# HealcareSystem.net
KiCad netlist of a schematic drawn in Altium Designer
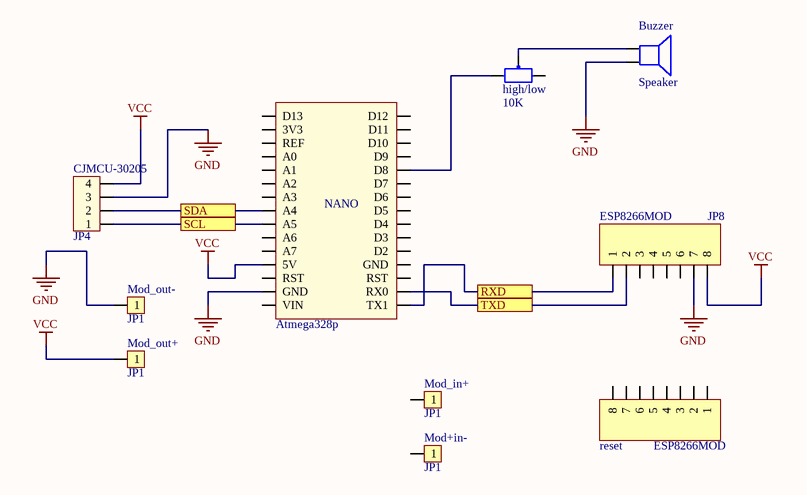
[diagram p0: HealcareSystem.SchDoc]

(export (version "E")
  (design (tool "Eeschema 10.0.6"))
  (components
    (comp (ref "Atmega328p")
      (value "Arduino Nano")
      (footprint "Arduino Nano")
      (description "Arduino NANO")
      (libsource (lib "LIBRARY") (part "Arduino Nano"))
    )
    (comp (ref "Buzzer")
      (value "Speaker")
      (footprint "SPEAKER")
      (description "Loudspeaker")
      (fields (field (name "PUBLISHER") "Altium Limited"))
      (libsource (lib "LIBRARY") (part "Speaker"))
    )
    (comp (ref "CJMCU-30205")
      (value "JP4")
      (footprint "CON4")
      (description "Connector 4")
      (libsource (lib "Library AL") (part "Con4"))
    )
    (comp (ref "ESP8266MOD")
      (value "JP8")
      (footprint "JP8-C1T")
      (description "WR-PHD 2.54 mm Angled Socket Header")
      (fields
        (field (name "MANUFACTURER") "Würth Elektronik eiSos GmbH")
        (field (name "PARTNO") "613008143121")
        (field (name "CREATED BY") "Karrer Zheng")
      )
      (libsource (lib "Library1") (part "JP8"))
    )
    (comp (ref "high/low")
      (value "10K")
      (footprint "VR")
      (description "Var Resistor")
      (libsource (lib "Library AL") (part "VR"))
    )
    (comp (ref "Mod+in-")
      (value "JP1")
      (footprint "JP1-D1T")
      (description "WR-PHD 2.54 mm Angled Socket Header")
      (fields
        (field (name "MANUFACTURER") "Würth Elektronik eiSos GmbH")
        (field (name "PARTNO") "613002143121")
        (field (name "CREATED BY") "Karrer Zheng")
      )
      (libsource (lib "LIBRARY") (part "JP1"))
    )
    (comp (ref "Mod_in+")
      (value "JP1")
      (footprint "JP1-D1T")
      (description "WR-PHD 2.54 mm Angled Socket Header")
      (fields
        (field (name "MANUFACTURER") "Würth Elektronik eiSos GmbH")
        (field (name "PARTNO") "613002143121")
        (field (name "CREATED BY") "Karrer Zheng")
      )
      (libsource (lib "LIBRARY") (part "JP1"))
    )
    (comp (ref "Mod_out+")
      (value "JP1")
      (footprint "JP1-D1T")
      (description "WR-PHD 2.54 mm Angled Socket Header")
      (fields
        (field (name "MANUFACTURER") "Würth Elektronik eiSos GmbH")
        (field (name "PARTNO") "613002143121")
        (field (name "CREATED BY") "Karrer Zheng")
      )
      (libsource (lib "LIBRARY") (part "JP1"))
    )
    (comp (ref "Mod_out-")
      (value "JP1")
      (footprint "JP1-D1T")
      (description "WR-PHD 2.54 mm Angled Socket Header")
      (fields
        (field (name "MANUFACTURER") "Würth Elektronik eiSos GmbH")
        (field (name "PARTNO") "613002143121")
        (field (name "CREATED BY") "Karrer Zheng")
      )
      (libsource (lib "LIBRARY") (part "JP1"))
    )
    (comp (ref "reset")
      (value "ESP8266MOD")
      (footprint "JP8-C1T")
      (description "WR-PHD 2.54 mm Angled Socket Header")
      (fields
        (field (name "MANUFACTURER") "Würth Elektronik eiSos GmbH")
        (field (name "PARTNO") "613008143121")
        (field (name "CREATED BY") "Karrer Zheng")
      )
      (libsource (lib "") (part "JP8_1"))
    )
  )
  (nets
    (net (code "1") (name "/RXD") (class "Default")
      (node (ref "Atmega328p") (pin "TX1") (pinfunction "TX1_TX1") (pintype "passive"))
      (node (ref "ESP8266MOD") (pin "1") (pinfunction "1_1") (pintype "passive"))
    )
    (net (code "2") (name "/SCL") (class "Default")
      (node (ref "Atmega328p") (pin "A5") (pinfunction "A5_A5") (pintype "passive"))
      (node (ref "CJMCU-30205") (pin "1") (pinfunction "1_1") (pintype "passive"))
    )
    (net (code "3") (name "/SDA") (class "Default")
      (node (ref "Atmega328p") (pin "A4") (pinfunction "A4_A4") (pintype "passive"))
      (node (ref "CJMCU-30205") (pin "2") (pinfunction "2_2") (pintype "passive"))
    )
    (net (code "4") (name "/TXD") (class "Default")
      (node (ref "Atmega328p") (pin "RX0") (pinfunction "RX0_RX0") (pintype "passive"))
      (node (ref "ESP8266MOD") (pin "2") (pinfunction "2_2") (pintype "passive"))
    )
    (net (code "5") (name "GND") (class "Default")
      (node (ref "Atmega328p") (pin "GND") (pinfunction "GND_GND") (pintype "passive"))
      (node (ref "Buzzer") (pin "2") (pinfunction "2_2") (pintype "passive"))
      (node (ref "CJMCU-30205") (pin "3") (pinfunction "3_3") (pintype "passive"))
      (node (ref "ESP8266MOD") (pin "7") (pinfunction "7_7") (pintype "passive"))
      (node (ref "Mod_out-") (pin "1") (pinfunction "1_1") (pintype "passive"))
    )
    (net (code "6") (name "Net-(Atmega328p-PadD8)") (class "Default")
      (node (ref "Atmega328p") (pin "D8") (pinfunction "D8_D8") (pintype "passive"))
      (node (ref "high/low") (pin "1") (pinfunction "1_1") (pintype "passive"))
    )
    (net (code "7") (name "Net-(Buzzer-Pad1)") (class "Default")
      (node (ref "Buzzer") (pin "1") (pinfunction "1_1") (pintype "passive"))
      (node (ref "high/low") (pin "2") (pinfunction "2_2") (pintype "passive"))
    )
    (net (code "8") (name "VCC") (class "Default")
      (node (ref "Atmega328p") (pin "5V") (pinfunction "5V_5V") (pintype "passive"))
      (node (ref "CJMCU-30205") (pin "4") (pinfunction "4_4") (pintype "passive"))
      (node (ref "ESP8266MOD") (pin "8") (pinfunction "8_8") (pintype "passive"))
      (node (ref "Mod_out+") (pin "1") (pinfunction "1_1") (pintype "passive"))
    )
    (net (code "9") (name "unconnected-(Atmega328p-Pad3V3)") (class "Default")
      (node (ref "Atmega328p") (pin "3V3") (pinfunction "3V3_3V3") (pintype "passive"))
    )
    (net (code "10") (name "unconnected-(Atmega328p-PadA0)") (class "Default")
      (node (ref "Atmega328p") (pin "A0") (pinfunction "A0_A0") (pintype "passive"))
    )
    (net (code "11") (name "unconnected-(Atmega328p-PadA1)") (class "Default")
      (node (ref "Atmega328p") (pin "A1") (pinfunction "A1_A1") (pintype "passive"))
    )
    (net (code "12") (name "unconnected-(Atmega328p-PadA2)") (class "Default")
      (node (ref "Atmega328p") (pin "A2") (pinfunction "A2_A2") (pintype "passive"))
    )
    (net (code "13") (name "unconnected-(Atmega328p-PadA3)") (class "Default")
      (node (ref "Atmega328p") (pin "A3") (pinfunction "A3_A3") (pintype "passive"))
    )
    (net (code "14") (name "unconnected-(Atmega328p-PadA6)") (class "Default")
      (node (ref "Atmega328p") (pin "A6") (pinfunction "A6_A6") (pintype "passive"))
    )
    (net (code "15") (name "unconnected-(Atmega328p-PadA7)") (class "Default")
      (node (ref "Atmega328p") (pin "A7") (pinfunction "A7_A7") (pintype "passive"))
    )
    (net (code "16") (name "unconnected-(Atmega328p-PadD2)") (class "Default")
      (node (ref "Atmega328p") (pin "D2") (pinfunction "D2_D2") (pintype "passive"))
    )
    (net (code "17") (name "unconnected-(Atmega328p-PadD3)") (class "Default")
      (node (ref "Atmega328p") (pin "D3") (pinfunction "D3_D3") (pintype "passive"))
    )
    (net (code "18") (name "unconnected-(Atmega328p-PadD4)") (class "Default")
      (node (ref "Atmega328p") (pin "D4") (pinfunction "D4_D4") (pintype "passive"))
    )
    (net (code "19") (name "unconnected-(Atmega328p-PadD5)") (class "Default")
      (node (ref "Atmega328p") (pin "D5") (pinfunction "D5_D5") (pintype "passive"))
    )
    (net (code "20") (name "unconnected-(Atmega328p-PadD6)") (class "Default")
      (node (ref "Atmega328p") (pin "D6") (pinfunction "D6_D6") (pintype "passive"))
    )
    (net (code "21") (name "unconnected-(Atmega328p-PadD7)") (class "Default")
      (node (ref "Atmega328p") (pin "D7") (pinfunction "D7_D7") (pintype "passive"))
    )
    (net (code "22") (name "unconnected-(Atmega328p-PadD9)") (class "Default")
      (node (ref "Atmega328p") (pin "D9") (pinfunction "D9_D9") (pintype "passive"))
    )
    (net (code "23") (name "unconnected-(Atmega328p-PadD10)") (class "Default")
      (node (ref "Atmega328p") (pin "D10") (pinfunction "D10_D10") (pintype "passive"))
    )
    (net (code "24") (name "unconnected-(Atmega328p-PadD11)") (class "Default")
      (node (ref "Atmega328p") (pin "D11") (pinfunction "D11_D11") (pintype "passive"))
    )
    (net (code "25") (name "unconnected-(Atmega328p-PadD12)") (class "Default")
      (node (ref "Atmega328p") (pin "D12") (pinfunction "D12_D12") (pintype "passive"))
    )
    (net (code "26") (name "unconnected-(Atmega328p-PadD13)") (class "Default")
      (node (ref "Atmega328p") (pin "D13") (pinfunction "D13_D13") (pintype "passive"))
    )
    (net (code "27") (name "unconnected-(Atmega328p-PadGND)") (class "Default")
      (node (ref "Atmega328p") (pin "GND") (pinfunction "GND_GND") (pintype "passive"))
    )
    (net (code "28") (name "unconnected-(Atmega328p-PadREF)") (class "Default")
      (node (ref "Atmega328p") (pin "REF") (pinfunction "REF_REF") (pintype "passive"))
    )
    (net (code "29") (name "unconnected-(Atmega328p-PadRST)") (class "Default")
      (node (ref "Atmega328p") (pin "RST") (pinfunction "RST_RST") (pintype "passive"))
    )
    (net (code "30") (name "unconnected-(Atmega328p-PadRST)_1") (class "Default")
      (node (ref "Atmega328p") (pin "RST") (pinfunction "RST_RST") (pintype "passive"))
    )
    (net (code "31") (name "unconnected-(Atmega328p-PadVIN)") (class "Default")
      (node (ref "Atmega328p") (pin "VIN") (pinfunction "VIN_VIN") (pintype "passive"))
    )
    (net (code "32") (name "unconnected-(ESP8266MOD-Pad3)") (class "Default")
      (node (ref "ESP8266MOD") (pin "3") (pinfunction "3_3") (pintype "passive"))
    )
    (net (code "33") (name "unconnected-(ESP8266MOD-Pad4)") (class "Default")
      (node (ref "ESP8266MOD") (pin "4") (pinfunction "4_4") (pintype "passive"))
    )
    (net (code "34") (name "unconnected-(ESP8266MOD-Pad5)") (class "Default")
      (node (ref "ESP8266MOD") (pin "5") (pinfunction "5_5") (pintype "passive"))
    )
    (net (code "35") (name "unconnected-(ESP8266MOD-Pad6)") (class "Default")
      (node (ref "ESP8266MOD") (pin "6") (pinfunction "6_6") (pintype "passive"))
    )
    (net (code "36") (name "unconnected-(Mod+in--Pad1)") (class "Default")
      (node (ref "Mod+in-") (pin "1") (pinfunction "1_1") (pintype "passive"))
    )
    (net (code "37") (name "unconnected-(Mod_in+-Pad1)") (class "Default")
      (node (ref "Mod_in+") (pin "1") (pinfunction "1_1") (pintype "passive"))
    )
    (net (code "38") (name "unconnected-(high/low-Pad3)") (class "Default")
      (node (ref "high/low") (pin "3") (pinfunction "3_3") (pintype "passive"))
    )
    (net (code "39") (name "unconnected-(reset-Pad1)") (class "Default")
      (node (ref "reset") (pin "1") (pinfunction "1_1") (pintype "passive"))
    )
    (net (code "40") (name "unconnected-(reset-Pad2)") (class "Default")
      (node (ref "reset") (pin "2") (pinfunction "2_2") (pintype "passive"))
    )
    (net (code "41") (name "unconnected-(reset-Pad3)") (class "Default")
      (node (ref "reset") (pin "3") (pinfunction "3_3") (pintype "passive"))
    )
    (net (code "42") (name "unconnected-(reset-Pad4)") (class "Default")
      (node (ref "reset") (pin "4") (pinfunction "4_4") (pintype "passive"))
    )
    (net (code "43") (name "unconnected-(reset-Pad5)") (class "Default")
      (node (ref "reset") (pin "5") (pinfunction "5_5") (pintype "passive"))
    )
    (net (code "44") (name "unconnected-(reset-Pad6)") (class "Default")
      (node (ref "reset") (pin "6") (pinfunction "6_6") (pintype "passive"))
    )
    (net (code "45") (name "unconnected-(reset-Pad7)") (class "Default")
      (node (ref "reset") (pin "7") (pinfunction "7_7") (pintype "passive"))
    )
    (net (code "46") (name "unconnected-(reset-Pad8)") (class "Default")
      (node (ref "reset") (pin "8") (pinfunction "8_8") (pintype "passive"))
    )
  )
)
